# Sheet1.net
KiCad netlist of a schematic drawn in Altium Designer
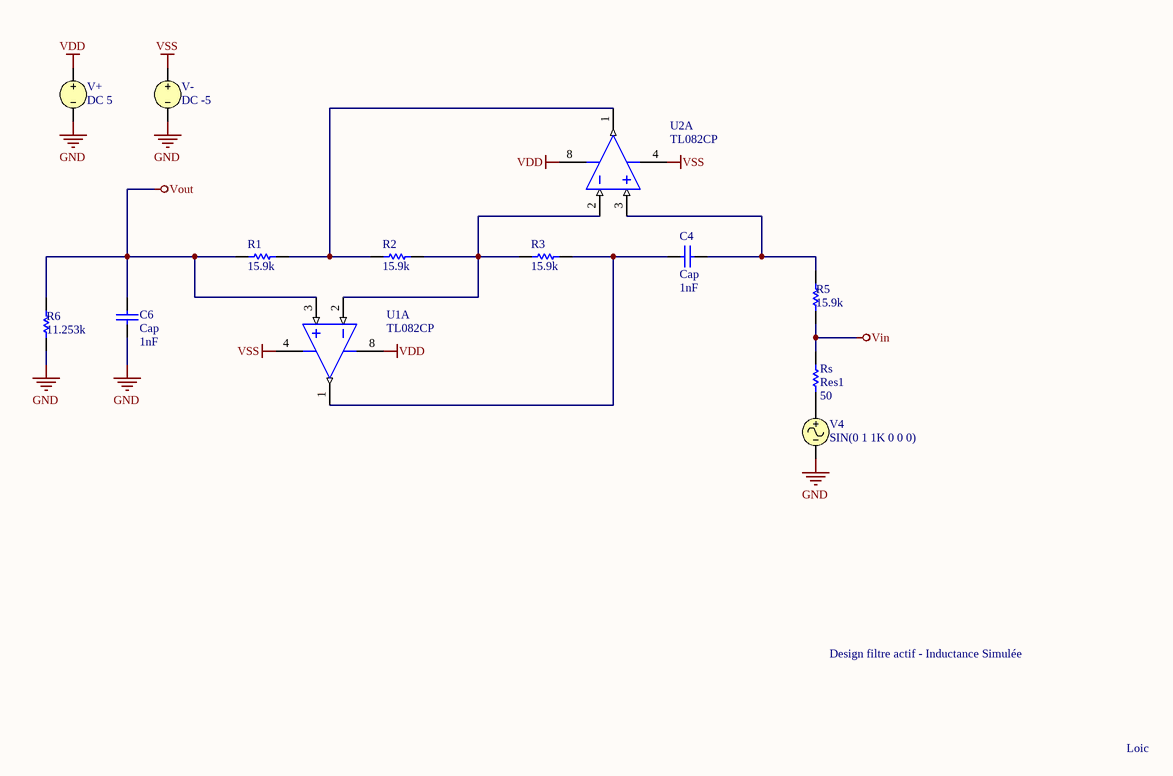
[diagram p0: Sheet1.SchDoc]

(export (version "E")
  (design (tool "Eeschema 10.0.6"))
  (components
    (comp (ref "C4")
      (value "Cap")
      (footprint "RAD-0.3")
      (description "Capacitor")
      (fields (field (name "ALTIUM_VALUE") "1nF") (field (name "PUBLISHER") "Altium Limited"))
      (libsource (lib "Miscellaneous Devices") (part "Cap"))
    )
    (comp (ref "C6")
      (value "Cap")
      (footprint "RAD-0.3")
      (description "Capacitor")
      (fields (field (name "ALTIUM_VALUE") "1nF") (field (name "PUBLISHER") "Altium Limited"))
      (libsource (lib "Miscellaneous Devices") (part "Cap"))
    )
    (comp (ref "R1")
      (value "15.9k")
      (footprint "AXIAL-0.3")
      (description "Resistor")
      (fields (field (name "Comment") "Res1") (field (name "PUBLISHER") "Altium Limited"))
      (libsource (lib "Miscellaneous Devices") (part "Res1"))
    )
    (comp (ref "R2")
      (value "15.9k")
      (footprint "AXIAL-0.3")
      (description "Resistor")
      (fields (field (name "Comment") "Res1") (field (name "PUBLISHER") "Altium Limited"))
      (libsource (lib "Miscellaneous Devices") (part "Res1"))
    )
    (comp (ref "R3")
      (value "15.9k")
      (footprint "AXIAL-0.3")
      (description "Resistor")
      (fields (field (name "Comment") "Res1") (field (name "PUBLISHER") "Altium Limited"))
      (libsource (lib "Miscellaneous Devices") (part "Res1"))
    )
    (comp (ref "R5")
      (value "15.9k")
      (footprint "AXIAL-0.3")
      (description "Resistor")
      (fields (field (name "Comment") "Res1") (field (name "PUBLISHER") "Altium Limited"))
      (libsource (lib "Miscellaneous Devices") (part "Res1"))
    )
    (comp (ref "R6")
      (value "11.253k")
      (footprint "AXIAL-0.3")
      (description "Resistor")
      (fields (field (name "Comment") "Res1") (field (name "PUBLISHER") "Altium Limited"))
      (libsource (lib "Miscellaneous Devices") (part "Res1"))
    )
    (comp (ref "Rs")
      (value "Res1")
      (footprint "AXIAL-0.3")
      (description "Resistor")
      (fields (field (name "ALTIUM_VALUE") "50") (field (name "PUBLISHER") "Altium Limited"))
      (libsource (lib "Miscellaneous Devices") (part "Res1"))
    )
    (comp (ref "U1")
      (value "TL082CP")
      (footprint "N08E")
      (description "Wide Bandwidth Dual JFET Input Operational Amplifier")
      (fields
        (field (name "MANUFACTURER") "National Semiconductor")
        (field (name "PUBLISHER") "Altium Limited")
      )
      (libsource (lib "NSC Amplifier") (part "TL082CP"))
    )
    (comp (ref "U2")
      (value "TL082CP")
      (footprint "N08E")
      (description "Wide Bandwidth Dual JFET Input Operational Amplifier")
      (fields
        (field (name "MANUFACTURER") "National Semiconductor")
        (field (name "PUBLISHER") "Altium Limited")
      )
      (libsource (lib "NSC Amplifier") (part "TL082CP"))
    )
    (comp (ref "V+")
      (value "DC 5")
      (description "Voltage Source")
      (fields (field (name "PUBLISHER") "Altium Limited"))
      (libsource (lib "Simulation Sources") (part "VSRC"))
    )
    (comp (ref "V-")
      (value "DC -5")
      (description "Voltage Source")
      (fields (field (name "PUBLISHER") "Altium Limited"))
      (libsource (lib "Simulation Sources") (part "VSRC"))
    )
    (comp (ref "V4")
      (value "SIN(0 1 1K 0 0 0)")
      (description "Sinusoidal Voltage Source")
      (fields (field (name "PUBLISHER") "Altium Limited"))
      (libsource (lib "Simulation Sources") (part "VSIN"))
    )
  )
  (nets
    (net (code "1") (name "GND") (class "Default")
      (node (ref "C6") (pin "2") (pinfunction "2_2") (pintype "passive"))
      (node (ref "R6") (pin "1") (pinfunction "1_1") (pintype "passive"))
      (node (ref "V+") (pin "2") (pinfunction "2_2") (pintype "passive"))
      (node (ref "V-") (pin "2") (pinfunction "2_2") (pintype "passive"))
      (node (ref "V4") (pin "2") (pinfunction "2_2") (pintype "passive"))
    )
    (net (code "2") (name "Net-(Rs-Pad1)") (class "Default")
      (node (ref "Rs") (pin "1") (pinfunction "1_1") (pintype "passive"))
      (node (ref "V4") (pin "1") (pinfunction "1_1") (pintype "passive"))
    )
    (net (code "3") (name "Net-(U1A-INA-)") (class "Default")
      (node (ref "R2") (pin "1") (pinfunction "1_1") (pintype "passive"))
      (node (ref "R3") (pin "2") (pinfunction "2_2") (pintype "passive"))
      (node (ref "U1") (pin "2") (pinfunction "INA-_2") (pintype "input"))
      (node (ref "U2") (pin "2") (pinfunction "INA-_2") (pintype "input"))
    )
    (net (code "4") (name "Net-(U1A-OUTA)") (class "Default")
      (node (ref "C4") (pin "1") (pinfunction "1_1") (pintype "passive"))
      (node (ref "R3") (pin "1") (pinfunction "1_1") (pintype "passive"))
      (node (ref "U1") (pin "1") (pinfunction "OUTA_1") (pintype "output"))
    )
    (net (code "5") (name "Net-(U2A-INA+)") (class "Default")
      (node (ref "C4") (pin "2") (pinfunction "2_2") (pintype "passive"))
      (node (ref "R5") (pin "2") (pinfunction "2_2") (pintype "passive"))
      (node (ref "U2") (pin "3") (pinfunction "INA+_3") (pintype "input"))
    )
    (net (code "6") (name "Net-(U2A-OUTA)") (class "Default")
      (node (ref "R1") (pin "1") (pinfunction "1_1") (pintype "passive"))
      (node (ref "R2") (pin "2") (pinfunction "2_2") (pintype "passive"))
      (node (ref "U2") (pin "1") (pinfunction "OUTA_1") (pintype "output"))
    )
    (net (code "7") (name "VDD") (class "Default")
      (node (ref "U1") (pin "8") (pinfunction "V+_8") (pintype "power_in"))
      (node (ref "U2") (pin "8") (pinfunction "V+_8") (pintype "power_in"))
      (node (ref "V+") (pin "1") (pinfunction "1_1") (pintype "passive"))
    )
    (net (code "8") (name "VSS") (class "Default")
      (node (ref "U1") (pin "4") (pinfunction "V-_4") (pintype "power_in"))
      (node (ref "U2") (pin "4") (pinfunction "V-_4") (pintype "power_in"))
      (node (ref "V-") (pin "1") (pinfunction "1_1") (pintype "passive"))
    )
    (net (code "9") (name "Vin") (class "Default")
      (node (ref "R5") (pin "1") (pinfunction "1_1") (pintype "passive"))
      (node (ref "Rs") (pin "2") (pinfunction "2_2") (pintype "passive"))
    )
    (net (code "10") (name "Vout") (class "Default")
      (node (ref "C6") (pin "1") (pinfunction "1_1") (pintype "passive"))
      (node (ref "R1") (pin "2") (pinfunction "2_2") (pintype "passive"))
      (node (ref "R6") (pin "2") (pinfunction "2_2") (pintype "passive"))
      (node (ref "U1") (pin "3") (pinfunction "INA+_3") (pintype "input"))
    )
  )
)
